# 23_LMS2_RX1_BB_ADC.net
KiCad netlist of a schematic drawn in Altium Designer
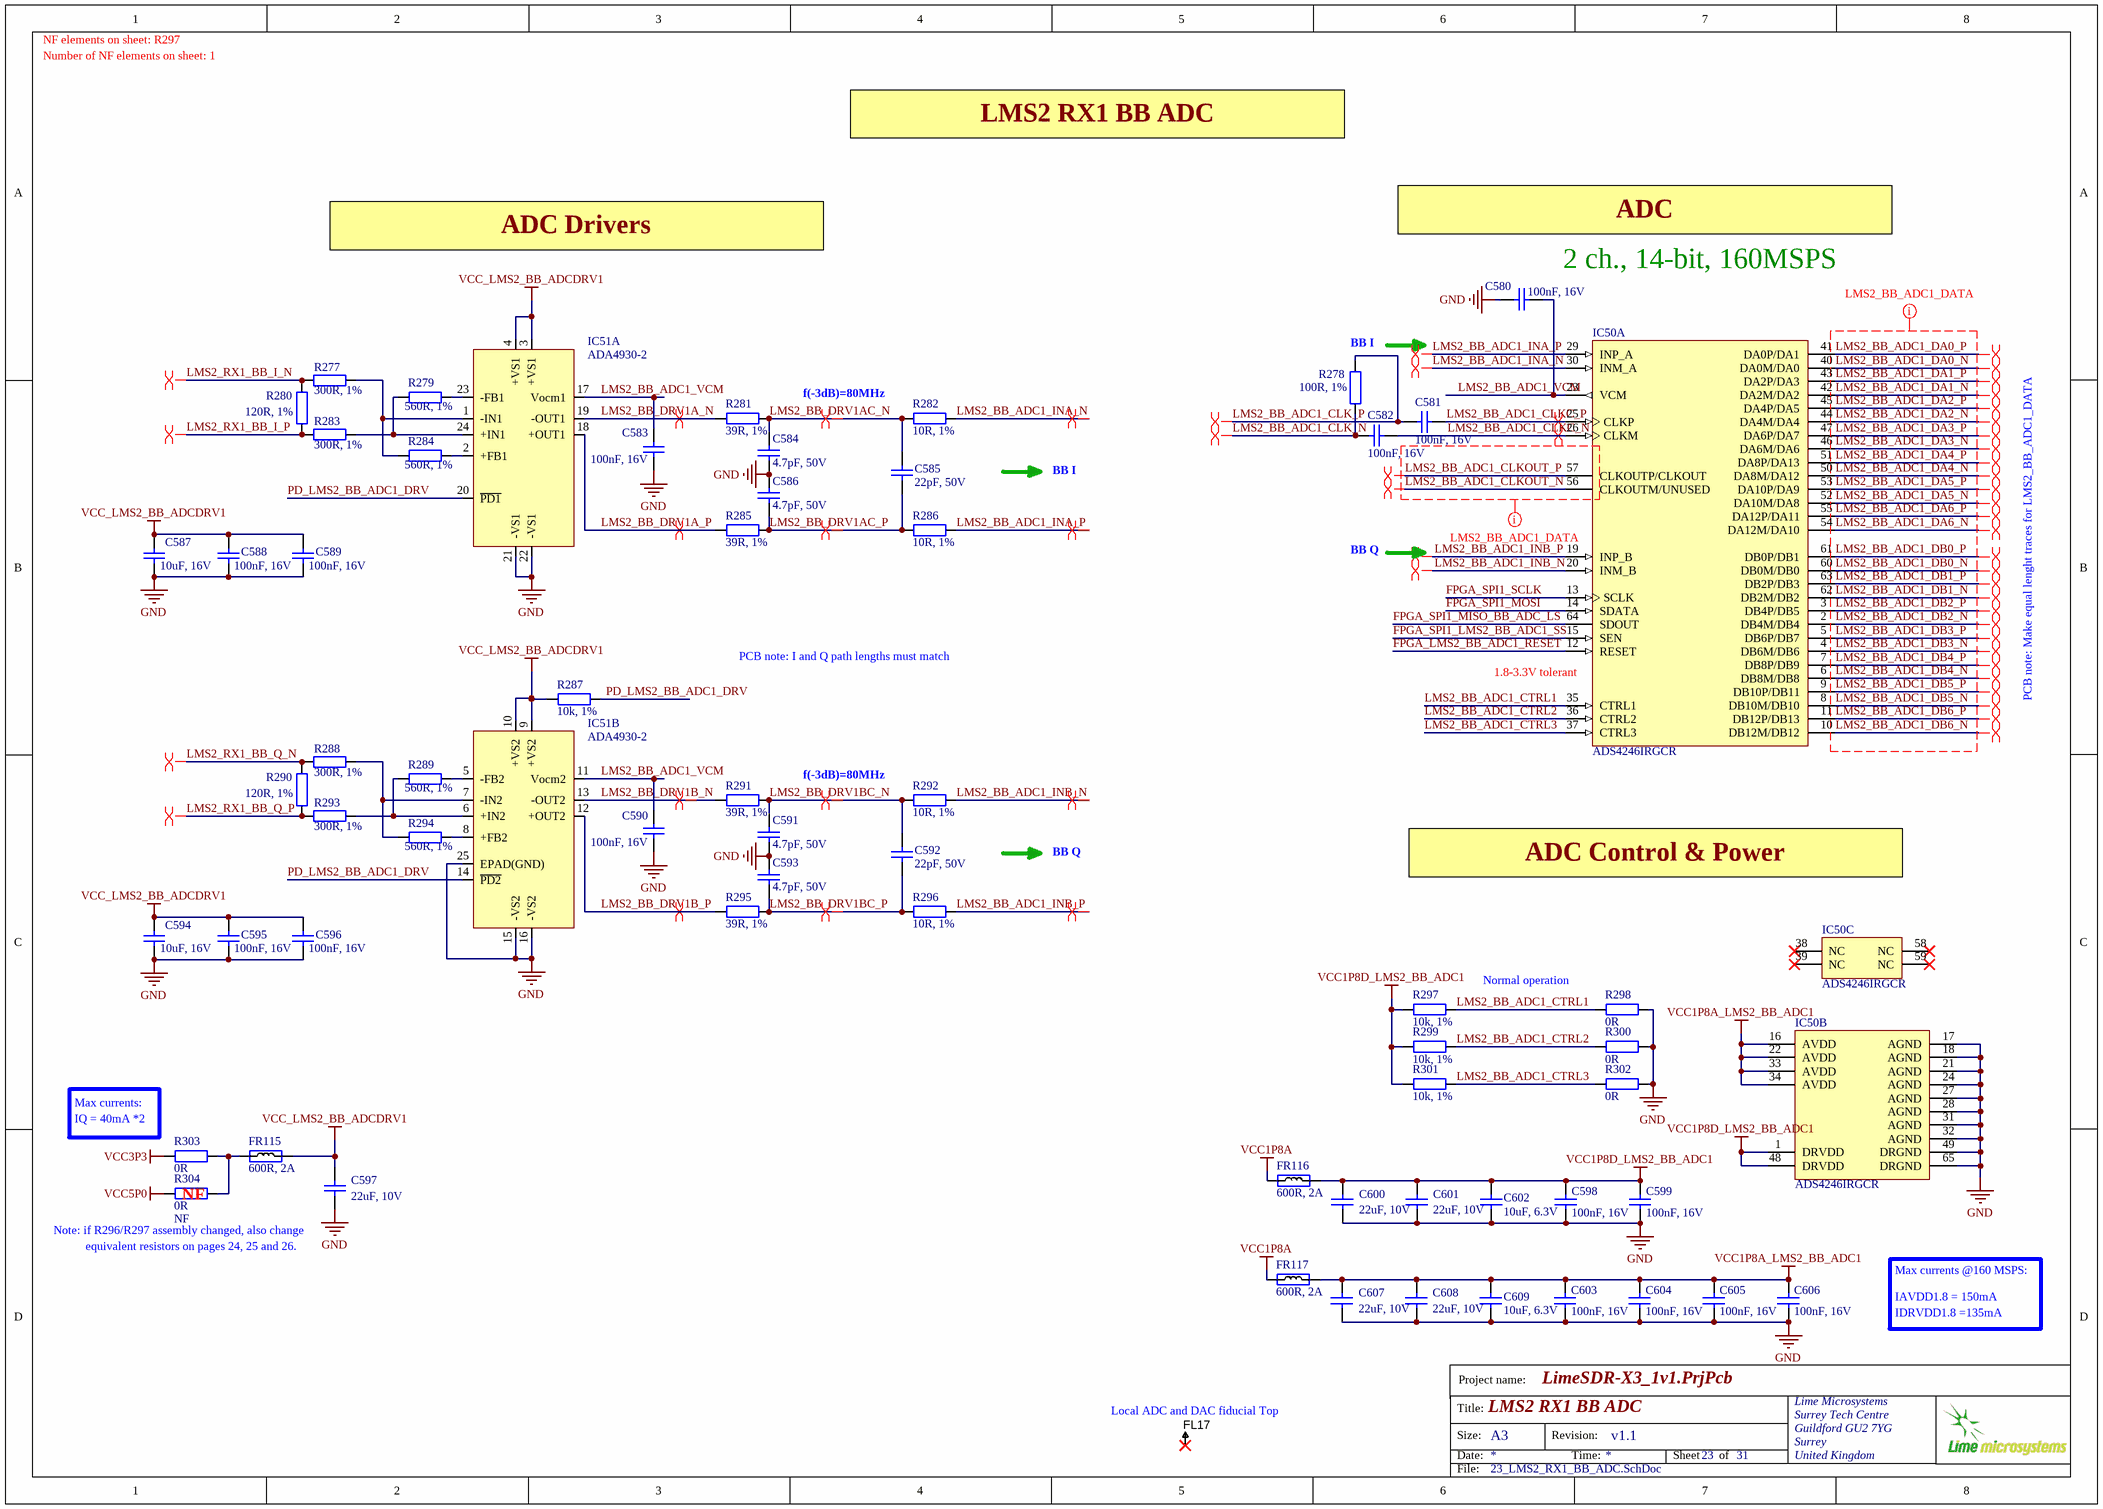
[diagram p0: 23_LMS2_RX1_BB_ADC.SchDoc]

(export (version "E")
  (design (tool "Eeschema 10.0.6"))
  (components
    (comp (ref "C580")
      (value "100nF, 16V")
      (footprint "CAP0402")
      (fields (field (name "TOLERANCE") "10 %") (field (name "MANUFACTURER") "Murata Electronics"))
      (libsource (lib "") (part "Cap_0603_2"))
    )
    (comp (ref "C581")
      (value "100nF, 16V")
      (footprint "CAP0402")
      (fields (field (name "TOLERANCE") "10 %") (field (name "MANUFACTURER") "Murata Electronics"))
      (libsource (lib "") (part "Cap_0603_2"))
    )
    (comp (ref "C582")
      (value "100nF, 16V")
      (footprint "CAP0402")
      (fields (field (name "TOLERANCE") "10 %") (field (name "MANUFACTURER") "Murata Electronics"))
      (libsource (lib "LimeFPGAboard_schLib") (part "Cap_0603"))
    )
    (comp (ref "C583")
      (value "100nF, 16V")
      (footprint "CAP0402")
      (fields (field (name "TOLERANCE") "10 %") (field (name "MANUFACTURER") "Murata Electronics"))
      (libsource (lib "LimeFPGAboard_schLib") (part "Cap_0603"))
    )
    (comp (ref "C584")
      (value "4.7pF, 50V")
      (footprint "CAP0402")
      (fields (field (name "MANUFACTURER") "MURATA"))
      (libsource (lib "LimeMicroAltiumLib_schLib") (part "Cap_0402"))
    )
    (comp (ref "C585")
      (value "22pF, 50V")
      (footprint "CAP0402")
      (fields (field (name "TOLERANCE") "±5%") (field (name "MANUFACTURER") "Yageo"))
      (libsource (lib "") (part "Cap_0402_1"))
    )
    (comp (ref "C586")
      (value "4.7pF, 50V")
      (footprint "CAP0402")
      (fields (field (name "MANUFACTURER") "MURATA"))
      (libsource (lib "LimeMicroAltiumLib_schLib") (part "Cap_0402"))
    )
    (comp (ref "C587")
      (value "10uF, 16V")
      (footprint "CAP0603")
      (fields (field (name "MANUFACTURER") "Yageo") (field (name "TOLERANCE") "±20%"))
      (libsource (lib "LimeMicroAltiumLib_schLib") (part "Cap_0603"))
    )
    (comp (ref "C588")
      (value "100nF, 16V")
      (footprint "CAP0402")
      (fields (field (name "TOLERANCE") "10 %") (field (name "MANUFACTURER") "Murata Electronics"))
      (libsource (lib "LimeFPGAboard_schLib") (part "Cap_0603"))
    )
    (comp (ref "C589")
      (value "100nF, 16V")
      (footprint "CAP0402")
      (fields (field (name "TOLERANCE") "10 %") (field (name "MANUFACTURER") "Murata Electronics"))
      (libsource (lib "LimeFPGAboard_schLib") (part "Cap_0603"))
    )
    (comp (ref "C590")
      (value "100nF, 16V")
      (footprint "CAP0402")
      (fields (field (name "TOLERANCE") "10 %") (field (name "MANUFACTURER") "Murata Electronics"))
      (libsource (lib "") (part "Cap_0603_6"))
    )
    (comp (ref "C591")
      (value "4.7pF, 50V")
      (footprint "CAP0402")
      (fields (field (name "MANUFACTURER") "MURATA"))
      (libsource (lib "LimeMicroAltiumLib_schLib") (part "Cap_0402"))
    )
    (comp (ref "C592")
      (value "22pF, 50V")
      (footprint "CAP0402")
      (fields (field (name "TOLERANCE") "±5%") (field (name "MANUFACTURER") "Yageo"))
      (libsource (lib "") (part "Cap_0402_1"))
    )
    (comp (ref "C593")
      (value "4.7pF, 50V")
      (footprint "CAP0402")
      (fields (field (name "MANUFACTURER") "MURATA"))
      (libsource (lib "LimeMicroAltiumLib_schLib") (part "Cap_0402"))
    )
    (comp (ref "C594")
      (value "10uF, 16V")
      (footprint "CAP0603")
      (fields (field (name "MANUFACTURER") "Yageo") (field (name "TOLERANCE") "±20%"))
      (libsource (lib "LimeMicroAltiumLib_schLib") (part "Cap_0603"))
    )
    (comp (ref "C595")
      (value "100nF, 16V")
      (footprint "CAP0402")
      (fields (field (name "TOLERANCE") "10 %") (field (name "MANUFACTURER") "Murata Electronics"))
      (libsource (lib "LimeFPGAboard_schLib") (part "Cap_0603"))
    )
    (comp (ref "C596")
      (value "100nF, 16V")
      (footprint "CAP0402")
      (fields (field (name "TOLERANCE") "10 %") (field (name "MANUFACTURER") "Murata Electronics"))
      (libsource (lib "LimeFPGAboard_schLib") (part "Cap_0603"))
    )
    (comp (ref "C597")
      (value "22uF, 10V")
      (footprint "CAP0603")
      (fields (field (name "TOLERANCE") "20 %") (field (name "MANUFACTURER") "TDK Corporation"))
      (libsource (lib "") (part "Cap_0603_7"))
    )
    (comp (ref "C598")
      (value "100nF, 16V")
      (footprint "CAP0402")
      (fields (field (name "TOLERANCE") "10 %") (field (name "MANUFACTURER") "Murata Electronics"))
      (libsource (lib "") (part "Cap_0603_5"))
    )
    (comp (ref "C599")
      (value "100nF, 16V")
      (footprint "CAP0402")
      (fields (field (name "TOLERANCE") "10 %") (field (name "MANUFACTURER") "Murata Electronics"))
      (libsource (lib "") (part "Cap_0603_5"))
    )
    (comp (ref "C600")
      (value "22uF, 10V")
      (footprint "CAP0603")
      (fields (field (name "TOLERANCE") "20 %") (field (name "MANUFACTURER") "TDK Corporation"))
      (libsource (lib "") (part "Cap_0603_5"))
    )
    (comp (ref "C601")
      (value "22uF, 10V")
      (footprint "CAP0603")
      (fields (field (name "TOLERANCE") "20 %") (field (name "MANUFACTURER") "TDK Corporation"))
      (libsource (lib "") (part "Cap_0603_5"))
    )
    (comp (ref "C602")
      (value "10uF, 6.3V")
      (footprint "CAP0603")
      (fields (field (name "TOLERANCE") "±20%") (field (name "MANUFACTURER") "Yageo"))
      (libsource (lib "") (part "Cap_0603_1"))
    )
    (comp (ref "C603")
      (value "100nF, 16V")
      (footprint "CAP0402")
      (fields (field (name "TOLERANCE") "10 %") (field (name "MANUFACTURER") "Murata Electronics"))
      (libsource (lib "") (part "Cap_0603_3"))
    )
    (comp (ref "C604")
      (value "100nF, 16V")
      (footprint "CAP0402")
      (fields (field (name "TOLERANCE") "10 %") (field (name "MANUFACTURER") "Murata Electronics"))
      (libsource (lib "") (part "Cap_0603_3"))
    )
    (comp (ref "C605")
      (value "100nF, 16V")
      (footprint "CAP0402")
      (fields (field (name "TOLERANCE") "10 %") (field (name "MANUFACTURER") "Murata Electronics"))
      (libsource (lib "") (part "Cap_0603_3"))
    )
    (comp (ref "C606")
      (value "100nF, 16V")
      (footprint "CAP0402")
      (fields (field (name "TOLERANCE") "10 %") (field (name "MANUFACTURER") "Murata Electronics"))
      (libsource (lib "") (part "Cap_0603_3"))
    )
    (comp (ref "C607")
      (value "22uF, 10V")
      (footprint "CAP0603")
      (fields (field (name "TOLERANCE") "20 %") (field (name "MANUFACTURER") "TDK Corporation"))
      (libsource (lib "") (part "Cap_0603_3"))
    )
    (comp (ref "C608")
      (value "22uF, 10V")
      (footprint "CAP0603")
      (fields (field (name "TOLERANCE") "20 %") (field (name "MANUFACTURER") "TDK Corporation"))
      (libsource (lib "") (part "Cap_0603_3"))
    )
    (comp (ref "C609")
      (value "10uF, 6.3V")
      (footprint "CAP0603")
      (fields (field (name "TOLERANCE") "±20%") (field (name "MANUFACTURER") "Yageo"))
      (libsource (lib "") (part "Cap_0603_4"))
    )
    (comp (ref "FL17")
      (value "Fiducial")
      (footprint "Fiducial_local")
      (libsource (lib "LimeMicroAltiumLib_schLib") (part "Fiducial"))
    )
    (comp (ref "FR115")
      (value "600R, 2A")
      (footprint "RES0805")
      (fields (field (name "MANUFACTURER") "TDK Corporation"))
      (libsource (lib "LimeMicroAltiumLib_schLib") (part "Ferrite"))
    )
    (comp (ref "FR116")
      (value "600R, 2A")
      (footprint "RES0805")
      (fields (field (name "MANUFACTURER") "TDK Corporation"))
      (libsource (lib "LimeFPGAboard_schLib") (part "Ferrite"))
    )
    (comp (ref "FR117")
      (value "600R, 2A")
      (footprint "RES0805")
      (fields (field (name "MANUFACTURER") "TDK Corporation"))
      (libsource (lib "LimeFPGAboard_schLib") (part "Ferrite"))
    )
    (comp (ref "IC50")
      (value "ADS4246IRGCR")
      (footprint "TI-RGC64-7400X7400TP_V")
      (description "14-Bit 160 MSPS Dual Low Power ADC, -40 to 85 degC, 64-pin QFN (RGC64), Green (RoHS & no Sb/Br)")
      (fields (field (name "MANUFACTURER") "Texas Instruments"))
      (libsource (lib "") (part "ADS4246IRGCR_1"))
    )
    (comp (ref "IC51")
      (value "ADA4930-2")
      (footprint "ADA4930-2_LFCSP-24")
      (fields (field (name "MANUFACTURER") "Analog Devices Inc."))
      (libsource (lib "LimeMicroAltiumLib_schLib") (part "ADA4930-2"))
    )
    (comp (ref "R277")
      (value "300R, 1%")
      (footprint "RES0402")
      (fields (field (name "TOLERANCE") "±1%") (field (name "MANUFACTURER") "Vishay Dale"))
      (libsource (lib "LimeFPGAboard_schLib") (part "Res_0402"))
    )
    (comp (ref "R278")
      (value "100R, 1%")
      (footprint "RES0402")
      (fields (field (name "TOLERANCE") "±1%") (field (name "MANUFACTURER") "Stackpole Electronics Inc."))
      (libsource (lib "LimeFPGAboard_schLib") (part "Res_0402"))
    )
    (comp (ref "R279")
      (value "560R, 1%")
      (footprint "RES0402")
      (fields (field (name "TOLERANCE") "±1%") (field (name "MANUFACTURER") "Vishay Dale"))
      (libsource (lib "LimeFPGAboard_schLib") (part "Res_0402"))
    )
    (comp (ref "R280")
      (value "120R, 1%")
      (footprint "RES0402")
      (fields (field (name "MANUFACTURER") "Yageo") (field (name "TOLERANCE") "1%"))
      (libsource (lib "") (part "Res_0402_1"))
    )
    (comp (ref "R281")
      (value "39R, 1%")
      (footprint "RES0402")
      (fields (field (name "MANUFACTURER") "Yageo") (field (name "TOLERANCE") "1%"))
      (libsource (lib "LimeMicroAltiumLib_schLib") (part "Res_0402"))
    )
    (comp (ref "R282")
      (value "10R, 1%")
      (footprint "RES0402")
      (fields (field (name "TOLERANCE") "1%"))
      (libsource (lib "LimeMicroAltiumLib_schLib") (part "Res_0402"))
    )
    (comp (ref "R283")
      (value "300R, 1%")
      (footprint "RES0402")
      (fields (field (name "TOLERANCE") "±1%") (field (name "MANUFACTURER") "Vishay Dale"))
      (libsource (lib "LimeFPGAboard_schLib") (part "Res_0402"))
    )
    (comp (ref "R284")
      (value "560R, 1%")
      (footprint "RES0402")
      (fields (field (name "TOLERANCE") "±1%") (field (name "MANUFACTURER") "Vishay Dale"))
      (libsource (lib "LimeFPGAboard_schLib") (part "Res_0402"))
    )
    (comp (ref "R285")
      (value "39R, 1%")
      (footprint "RES0402")
      (fields (field (name "MANUFACTURER") "Yageo") (field (name "TOLERANCE") "1%"))
      (libsource (lib "LimeMicroAltiumLib_schLib") (part "Res_0402"))
    )
    (comp (ref "R286")
      (value "10R, 1%")
      (footprint "RES0402")
      (fields (field (name "TOLERANCE") "1%"))
      (libsource (lib "LimeMicroAltiumLib_schLib") (part "Res_0402"))
    )
    (comp (ref "R287")
      (value "10k, 1%")
      (footprint "RES0402")
      (fields (field (name "MANUFACTURER") "Yageo") (field (name "TOLERANCE") "±1%"))
      (libsource (lib "LimeMicroAltiumLib_schLib") (part "Res_0402"))
    )
    (comp (ref "R288")
      (value "300R, 1%")
      (footprint "RES0402")
      (fields (field (name "TOLERANCE") "±1%") (field (name "MANUFACTURER") "Vishay Dale"))
      (libsource (lib "LimeFPGAboard_schLib") (part "Res_0402"))
    )
    (comp (ref "R289")
      (value "560R, 1%")
      (footprint "RES0402")
      (fields (field (name "TOLERANCE") "±1%") (field (name "MANUFACTURER") "Vishay Dale"))
      (libsource (lib "LimeFPGAboard_schLib") (part "Res_0402"))
    )
    (comp (ref "R290")
      (value "120R, 1%")
      (footprint "RES0402")
      (fields (field (name "MANUFACTURER") "Yageo") (field (name "TOLERANCE") "1%"))
      (libsource (lib "") (part "Res_0402_1"))
    )
    (comp (ref "R291")
      (value "39R, 1%")
      (footprint "RES0402")
      (fields (field (name "MANUFACTURER") "Yageo") (field (name "TOLERANCE") "1%"))
      (libsource (lib "LimeMicroAltiumLib_schLib") (part "Res_0402"))
    )
    (comp (ref "R292")
      (value "10R, 1%")
      (footprint "RES0402")
      (fields (field (name "TOLERANCE") "1%"))
      (libsource (lib "LimeMicroAltiumLib_schLib") (part "Res_0402"))
    )
    (comp (ref "R293")
      (value "300R, 1%")
      (footprint "RES0402")
      (fields (field (name "TOLERANCE") "±1%") (field (name "MANUFACTURER") "Vishay Dale"))
      (libsource (lib "LimeFPGAboard_schLib") (part "Res_0402"))
    )
    (comp (ref "R294")
      (value "560R, 1%")
      (footprint "RES0402")
      (fields (field (name "TOLERANCE") "±1%") (field (name "MANUFACTURER") "Vishay Dale"))
      (libsource (lib "LimeFPGAboard_schLib") (part "Res_0402"))
    )
    (comp (ref "R295")
      (value "39R, 1%")
      (footprint "RES0402")
      (fields (field (name "MANUFACTURER") "Yageo") (field (name "TOLERANCE") "1%"))
      (libsource (lib "LimeMicroAltiumLib_schLib") (part "Res_0402"))
    )
    (comp (ref "R296")
      (value "10R, 1%")
      (footprint "RES0402")
      (fields (field (name "TOLERANCE") "1%"))
      (libsource (lib "LimeMicroAltiumLib_schLib") (part "Res_0402"))
    )
    (comp (ref "R297")
      (value "10k, 1%")
      (footprint "RES0402")
      (fields (field (name "MANUFACTURER") "Yageo") (field (name "TOLERANCE") "±1%"))
      (libsource (lib "LimeMicroAltiumLib_schLib") (part "Res_0402"))
    )
    (comp (ref "R298")
      (value "0R")
      (footprint "RES0402")
      (fields (field (name "MANUFACTURER") "Yageo"))
      (libsource (lib "LimeFPGAboard_schLib") (part "Res_0402"))
    )
    (comp (ref "R299")
      (value "10k, 1%")
      (footprint "RES0402")
      (fields (field (name "MANUFACTURER") "Yageo") (field (name "TOLERANCE") "±1%"))
      (libsource (lib "LimeMicroAltiumLib_schLib") (part "Res_0402"))
    )
    (comp (ref "R300")
      (value "0R")
      (footprint "RES0402")
      (fields (field (name "MANUFACTURER") "Yageo"))
      (libsource (lib "LimeFPGAboard_schLib") (part "Res_0402"))
    )
    (comp (ref "R301")
      (value "10k, 1%")
      (footprint "RES0402")
      (fields (field (name "MANUFACTURER") "Yageo") (field (name "TOLERANCE") "±1%"))
      (libsource (lib "LimeMicroAltiumLib_schLib") (part "Res_0402"))
    )
    (comp (ref "R302")
      (value "0R")
      (footprint "RES0402")
      (fields (field (name "MANUFACTURER") "Yageo"))
      (libsource (lib "LimeFPGAboard_schLib") (part "Res_0402"))
    )
    (comp (ref "R303")
      (value "0R")
      (footprint "RES0402")
      (fields (field (name "MANUFACTURER") "Yageo") (field (name "TOLERANCE") "Jumper"))
      (libsource (lib "LimeMicroAltiumLib_schLib") (part "Res_0402"))
    )
    (comp (ref "R304")
      (value "0R")
      (footprint "RES0402")
      (fields
        (field (name "ASSEMBLY INFO") "NF")
        (field (name "MANUFACTURER") "Yageo")
        (field (name "TOLERANCE") "Jumper")
      )
      (libsource (lib "LimeMicroAltiumLib_schLib") (part "Res_0402"))
    )
  )
  (nets
    (net (code "1") (name "/FPGA_LMS2_BB_ADC1_RESET") (class "Default")
      (node (ref "IC50") (pin "12") (pinfunction "RESET_12") (pintype "input"))
    )
    (net (code "2") (name "/FPGA_SPI1_LMS2_BB_ADC1_SS") (class "Default")
      (node (ref "IC50") (pin "15") (pinfunction "SEN_15") (pintype "input"))
    )
    (net (code "3") (name "/FPGA_SPI1_MISO_BB_ADC_LS") (class "Default")
      (node (ref "IC50") (pin "64") (pinfunction "SDOUT_64") (pintype "tri_state"))
    )
    (net (code "4") (name "/FPGA_SPI1_MOSI") (class "Default")
      (node (ref "IC50") (pin "14") (pinfunction "SDATA_14") (pintype "input"))
    )
    (net (code "5") (name "/FPGA_SPI1_SCLK") (class "Default")
      (node (ref "IC50") (pin "13") (pinfunction "SCLK_13") (pintype "input"))
    )
    (net (code "6") (name "/LMS2_BB_ADC1_CLKC_N") (class "Default")
      (node (ref "C582") (pin "1") (pinfunction "1_1") (pintype "passive"))
      (node (ref "IC50") (pin "26") (pinfunction "CLKM_26") (pintype "input"))
    )
    (net (code "7") (name "/LMS2_BB_ADC1_CLKC_P") (class "Default")
      (node (ref "C581") (pin "1") (pinfunction "1_1") (pintype "passive"))
      (node (ref "IC50") (pin "25") (pinfunction "CLKP_25") (pintype "input"))
    )
    (net (code "8") (name "/LMS2_BB_ADC1_CLKOUT_N") (class "Default")
      (node (ref "IC50") (pin "56") (pinfunction "CLKOUTM/UNUSED_56") (pintype "tri_state"))
    )
    (net (code "9") (name "/LMS2_BB_ADC1_CLKOUT_P") (class "Default")
      (node (ref "IC50") (pin "57") (pinfunction "CLKOUTP/CLKOUT_57") (pintype "tri_state"))
    )
    (net (code "10") (name "/LMS2_BB_ADC1_CLK_N") (class "Default")
      (node (ref "C582") (pin "2") (pinfunction "2_2") (pintype "passive"))
      (node (ref "R278") (pin "1") (pinfunction "1_1") (pintype "passive"))
    )
    (net (code "11") (name "/LMS2_BB_ADC1_CLK_P") (class "Default")
      (node (ref "C581") (pin "2") (pinfunction "2_2") (pintype "passive"))
      (node (ref "R278") (pin "2") (pinfunction "2_2") (pintype "passive"))
    )
    (net (code "12") (name "/LMS2_BB_ADC1_CTRL1") (class "Default")
      (node (ref "IC50") (pin "35") (pinfunction "CTRL1_35") (pintype "input"))
      (node (ref "R297") (pin "1") (pinfunction "1_1") (pintype "passive"))
      (node (ref "R298") (pin "2") (pinfunction "2_2") (pintype "passive"))
    )
    (net (code "13") (name "/LMS2_BB_ADC1_CTRL2") (class "Default")
      (node (ref "IC50") (pin "36") (pinfunction "CTRL2_36") (pintype "input"))
      (node (ref "R299") (pin "1") (pinfunction "1_1") (pintype "passive"))
      (node (ref "R300") (pin "2") (pinfunction "2_2") (pintype "passive"))
    )
    (net (code "14") (name "/LMS2_BB_ADC1_CTRL3") (class "Default")
      (node (ref "IC50") (pin "37") (pinfunction "CTRL3_37") (pintype "input"))
      (node (ref "R301") (pin "1") (pinfunction "1_1") (pintype "passive"))
      (node (ref "R302") (pin "2") (pinfunction "2_2") (pintype "passive"))
    )
    (net (code "15") (name "/LMS2_BB_ADC1_DA0_N") (class "Default")
      (node (ref "IC50") (pin "40") (pinfunction "DA0M/DA0_40") (pintype "tri_state"))
    )
    (net (code "16") (name "/LMS2_BB_ADC1_DA0_P") (class "Default")
      (node (ref "IC50") (pin "41") (pinfunction "DA0P/DA1_41") (pintype "tri_state"))
    )
    (net (code "17") (name "/LMS2_BB_ADC1_DA1_N") (class "Default")
      (node (ref "IC50") (pin "42") (pinfunction "DA2M/DA2_42") (pintype "tri_state"))
    )
    (net (code "18") (name "/LMS2_BB_ADC1_DA1_P") (class "Default")
      (node (ref "IC50") (pin "43") (pinfunction "DA2P/DA3_43") (pintype "tri_state"))
    )
    (net (code "19") (name "/LMS2_BB_ADC1_DA2_N") (class "Default")
      (node (ref "IC50") (pin "44") (pinfunction "DA4M/DA4_44") (pintype "tri_state"))
    )
    (net (code "20") (name "/LMS2_BB_ADC1_DA2_P") (class "Default")
      (node (ref "IC50") (pin "45") (pinfunction "DA4P/DA5_45") (pintype "tri_state"))
    )
    (net (code "21") (name "/LMS2_BB_ADC1_DA3_N") (class "Default")
      (node (ref "IC50") (pin "46") (pinfunction "DA6M/DA6_46") (pintype "tri_state"))
    )
    (net (code "22") (name "/LMS2_BB_ADC1_DA3_P") (class "Default")
      (node (ref "IC50") (pin "47") (pinfunction "DA6P/DA7_47") (pintype "tri_state"))
    )
    (net (code "23") (name "/LMS2_BB_ADC1_DA4_N") (class "Default")
      (node (ref "IC50") (pin "50") (pinfunction "DA8M/DA12_50") (pintype "tri_state"))
    )
    (net (code "24") (name "/LMS2_BB_ADC1_DA4_P") (class "Default")
      (node (ref "IC50") (pin "51") (pinfunction "DA8P/DA13_51") (pintype "tri_state"))
    )
    (net (code "25") (name "/LMS2_BB_ADC1_DA5_N") (class "Default")
      (node (ref "IC50") (pin "52") (pinfunction "DA10M/DA8_52") (pintype "tri_state"))
    )
    (net (code "26") (name "/LMS2_BB_ADC1_DA5_P") (class "Default")
      (node (ref "IC50") (pin "53") (pinfunction "DA10P/DA9_53") (pintype "tri_state"))
    )
    (net (code "27") (name "/LMS2_BB_ADC1_DA6_N") (class "Default")
      (node (ref "IC50") (pin "54") (pinfunction "DA12M/DA10_54") (pintype "tri_state"))
    )
    (net (code "28") (name "/LMS2_BB_ADC1_DA6_P") (class "Default")
      (node (ref "IC50") (pin "55") (pinfunction "DA12P/DA11_55") (pintype "tri_state"))
    )
    (net (code "29") (name "/LMS2_BB_ADC1_DB0_N") (class "Default")
      (node (ref "IC50") (pin "60") (pinfunction "DB0M/DB0_60") (pintype "tri_state"))
    )
    (net (code "30") (name "/LMS2_BB_ADC1_DB0_P") (class "Default")
      (node (ref "IC50") (pin "61") (pinfunction "DB0P/DB1_61") (pintype "tri_state"))
    )
    (net (code "31") (name "/LMS2_BB_ADC1_DB1_N") (class "Default")
      (node (ref "IC50") (pin "62") (pinfunction "DB2M/DB2_62") (pintype "tri_state"))
    )
    (net (code "32") (name "/LMS2_BB_ADC1_DB1_P") (class "Default")
      (node (ref "IC50") (pin "63") (pinfunction "DB2P/DB3_63") (pintype "tri_state"))
    )
    (net (code "33") (name "/LMS2_BB_ADC1_DB2_N") (class "Default")
      (node (ref "IC50") (pin "2") (pinfunction "DB4M/DB4_2") (pintype "tri_state"))
    )
    (net (code "34") (name "/LMS2_BB_ADC1_DB2_P") (class "Default")
      (node (ref "IC50") (pin "3") (pinfunction "DB4P/DB5_3") (pintype "tri_state"))
    )
    (net (code "35") (name "/LMS2_BB_ADC1_DB3_N") (class "Default")
      (node (ref "IC50") (pin "4") (pinfunction "DB6M/DB6_4") (pintype "tri_state"))
    )
    (net (code "36") (name "/LMS2_BB_ADC1_DB3_P") (class "Default")
      (node (ref "IC50") (pin "5") (pinfunction "DB6P/DB7_5") (pintype "tri_state"))
    )
    (net (code "37") (name "/LMS2_BB_ADC1_DB4_N") (class "Default")
      (node (ref "IC50") (pin "6") (pinfunction "DB8M/DB8_6") (pintype "tri_state"))
    )
    (net (code "38") (name "/LMS2_BB_ADC1_DB4_P") (class "Default")
      (node (ref "IC50") (pin "7") (pinfunction "DB8P/DB9_7") (pintype "tri_state"))
    )
    (net (code "39") (name "/LMS2_BB_ADC1_DB5_N") (class "Default")
      (node (ref "IC50") (pin "8") (pinfunction "DB10M/DB10_8") (pintype "tri_state"))
    )
    (net (code "40") (name "/LMS2_BB_ADC1_DB5_P") (class "Default")
      (node (ref "IC50") (pin "9") (pinfunction "DB10P/DB11_9") (pintype "tri_state"))
    )
    (net (code "41") (name "/LMS2_BB_ADC1_DB6_N") (class "Default")
      (node (ref "IC50") (pin "10") (pinfunction "DB12M/DB12_10") (pintype "tri_state"))
    )
    (net (code "42") (name "/LMS2_BB_ADC1_DB6_P") (class "Default")
      (node (ref "IC50") (pin "11") (pinfunction "DB12P/DB13_11") (pintype "tri_state"))
    )
    (net (code "43") (name "/LMS2_BB_ADC1_INA_N") (class "Default")
      (node (ref "IC50") (pin "30") (pinfunction "INM_A_30") (pintype "input"))
      (node (ref "R282") (pin "1") (pinfunction "1_1") (pintype "passive"))
    )
    (net (code "44") (name "/LMS2_BB_ADC1_INA_P") (class "Default")
      (node (ref "IC50") (pin "29") (pinfunction "INP_A_29") (pintype "input"))
      (node (ref "R286") (pin "1") (pinfunction "1_1") (pintype "passive"))
    )
    (net (code "45") (name "/LMS2_BB_ADC1_INB_N") (class "Default")
      (node (ref "IC50") (pin "20") (pinfunction "INM_B_20") (pintype "input"))
      (node (ref "R292") (pin "1") (pinfunction "1_1") (pintype "passive"))
    )
    (net (code "46") (name "/LMS2_BB_ADC1_INB_P") (class "Default")
      (node (ref "IC50") (pin "19") (pinfunction "INP_B_19") (pintype "input"))
      (node (ref "R296") (pin "1") (pinfunction "1_1") (pintype "passive"))
    )
    (net (code "47") (name "/LMS2_BB_ADC1_VCM") (class "Default")
      (node (ref "C580") (pin "2") (pinfunction "2_2") (pintype "passive"))
      (node (ref "C583") (pin "1") (pinfunction "1_1") (pintype "passive"))
      (node (ref "C590") (pin "1") (pinfunction "1_1") (pintype "passive"))
      (node (ref "IC50") (pin "23") (pinfunction "VCM_23") (pintype "output"))
      (node (ref "IC51") (pin "11") (pinfunction "Vocm2_11") (pintype "input"))
      (node (ref "IC51") (pin "17") (pinfunction "Vocm1_17") (pintype "input"))
    )
    (net (code "48") (name "/LMS2_BB_DRV1AC_N") (class "Default")
      (node (ref "C584") (pin "1") (pinfunction "1_1") (pintype "passive"))
      (node (ref "C585") (pin "1") (pinfunction "1_1") (pintype "passive"))
      (node (ref "R281") (pin "1") (pinfunction "1_1") (pintype "passive"))
      (node (ref "R282") (pin "2") (pinfunction "2_2") (pintype "passive"))
    )
    (net (code "49") (name "/LMS2_BB_DRV1AC_P") (class "Default")
      (node (ref "C585") (pin "2") (pinfunction "2_2") (pintype "passive"))
      (node (ref "C586") (pin "2") (pinfunction "2_2") (pintype "passive"))
      (node (ref "R285") (pin "1") (pinfunction "1_1") (pintype "passive"))
      (node (ref "R286") (pin "2") (pinfunction "2_2") (pintype "passive"))
    )
    (net (code "50") (name "/LMS2_BB_DRV1A_N") (class "Default")
      (node (ref "IC51") (pin "19") (pinfunction "-OUT1_19") (pintype "output"))
      (node (ref "R281") (pin "2") (pinfunction "2_2") (pintype "passive"))
    )
    (net (code "51") (name "/LMS2_BB_DRV1A_P") (class "Default")
      (node (ref "IC51") (pin "18") (pinfunction "+OUT1_18") (pintype "output"))
      (node (ref "R285") (pin "2") (pinfunction "2_2") (pintype "passive"))
    )
    (net (code "52") (name "/LMS2_BB_DRV1BC_N") (class "Default")
      (node (ref "C591") (pin "1") (pinfunction "1_1") (pintype "passive"))
      (node (ref "C592") (pin "1") (pinfunction "1_1") (pintype "passive"))
      (node (ref "R291") (pin "1") (pinfunction "1_1") (pintype "passive"))
      (node (ref "R292") (pin "2") (pinfunction "2_2") (pintype "passive"))
    )
    (net (code "53") (name "/LMS2_BB_DRV1BC_P") (class "Default")
      (node (ref "C592") (pin "2") (pinfunction "2_2") (pintype "passive"))
      (node (ref "C593") (pin "2") (pinfunction "2_2") (pintype "passive"))
      (node (ref "R295") (pin "1") (pinfunction "1_1") (pintype "passive"))
      (node (ref "R296") (pin "2") (pinfunction "2_2") (pintype "passive"))
    )
    (net (code "54") (name "/LMS2_BB_DRV1B_N") (class "Default")
      (node (ref "IC51") (pin "13") (pinfunction "-OUT2_13") (pintype "output"))
      (node (ref "R291") (pin "2") (pinfunction "2_2") (pintype "passive"))
    )
    (net (code "55") (name "/LMS2_BB_DRV1B_P") (class "Default")
      (node (ref "IC51") (pin "12") (pinfunction "+OUT2_12") (pintype "output"))
      (node (ref "R295") (pin "2") (pinfunction "2_2") (pintype "passive"))
    )
    (net (code "56") (name "/LMS2_RX1_BB_I_N") (class "Default")
      (node (ref "R277") (pin "2") (pinfunction "2_2") (pintype "passive"))
      (node (ref "R280") (pin "2") (pinfunction "2_2") (pintype "passive"))
    )
    (net (code "57") (name "/LMS2_RX1_BB_I_P") (class "Default")
      (node (ref "R280") (pin "1") (pinfunction "1_1") (pintype "passive"))
      (node (ref "R283") (pin "2") (pinfunction "2_2") (pintype "passive"))
    )
    (net (code "58") (name "/LMS2_RX1_BB_Q_N") (class "Default")
      (node (ref "R288") (pin "2") (pinfunction "2_2") (pintype "passive"))
      (node (ref "R290") (pin "2") (pinfunction "2_2") (pintype "passive"))
    )
    (net (code "59") (name "/LMS2_RX1_BB_Q_P") (class "Default")
      (node (ref "R290") (pin "1") (pinfunction "1_1") (pintype "passive"))
      (node (ref "R293") (pin "2") (pinfunction "2_2") (pintype "passive"))
    )
    (net (code "60") (name "/PD_LMS2_BB_ADC1_DRV") (class "Default")
      (node (ref "IC51") (pin "14") (pinfunction "~{PD2}_14") (pintype "input"))
      (node (ref "IC51") (pin "20") (pinfunction "~{PD1}_20") (pintype "input"))
      (node (ref "R287") (pin "1") (pinfunction "1_1") (pintype "passive"))
    )
    (net (code "61") (name "GND") (class "Default")
      (node (ref "C580") (pin "1") (pinfunction "1_1") (pintype "passive"))
      (node (ref "C583") (pin "2") (pinfunction "2_2") (pintype "passive"))
      (node (ref "C584") (pin "2") (pinfunction "2_2") (pintype "passive"))
      (node (ref "C586") (pin "1") (pinfunction "1_1") (pintype "passive"))
      (node (ref "C587") (pin "1") (pinfunction "1_1") (pintype "passive"))
      (node (ref "C588") (pin "2") (pinfunction "2_2") (pintype "passive"))
      (node (ref "C589") (pin "2") (pinfunction "2_2") (pintype "passive"))
      (node (ref "C590") (pin "2") (pinfunction "2_2") (pintype "passive"))
      (node (ref "C591") (pin "2") (pinfunction "2_2") (pintype "passive"))
      (node (ref "C593") (pin "1") (pinfunction "1_1") (pintype "passive"))
      (node (ref "C594") (pin "1") (pinfunction "1_1") (pintype "passive"))
      (node (ref "C595") (pin "2") (pinfunction "2_2") (pintype "passive"))
      (node (ref "C596") (pin "2") (pinfunction "2_2") (pintype "passive"))
      (node (ref "C597") (pin "1") (pinfunction "1_1") (pintype "passive"))
      (node (ref "C598") (pin "1") (pinfunction "1_1") (pintype "passive"))
      (node (ref "C599") (pin "1") (pinfunction "1_1") (pintype "passive"))
      (node (ref "C600") (pin "1") (pinfunction "1_1") (pintype "passive"))
      (node (ref "C601") (pin "1") (pinfunction "1_1") (pintype "passive"))
      (node (ref "C602") (pin "2") (pinfunction "2_2") (pintype "passive"))
      (node (ref "C603") (pin "1") (pinfunction "1_1") (pintype "passive"))
      (node (ref "C604") (pin "1") (pinfunction "1_1") (pintype "passive"))
      (node (ref "C605") (pin "1") (pinfunction "1_1") (pintype "passive"))
      (node (ref "C606") (pin "1") (pinfunction "1_1") (pintype "passive"))
      (node (ref "C607") (pin "1") (pinfunction "1_1") (pintype "passive"))
      (node (ref "C608") (pin "1") (pinfunction "1_1") (pintype "passive"))
      (node (ref "C609") (pin "2") (pinfunction "2_2") (pintype "passive"))
      (node (ref "IC50") (pin "17") (pinfunction "AGND_17") (pintype "power_in"))
      (node (ref "IC50") (pin "18") (pinfunction "AGND_18") (pintype "power_in"))
      (node (ref "IC50") (pin "21") (pinfunction "AGND_21") (pintype "power_in"))
      (node (ref "IC50") (pin "24") (pinfunction "AGND_24") (pintype "power_in"))
      (node (ref "IC50") (pin "27") (pinfunction "AGND_27") (pintype "power_in"))
      (node (ref "IC50") (pin "28") (pinfunction "AGND_28") (pintype "power_in"))
      (node (ref "IC50") (pin "31") (pinfunction "AGND_31") (pintype "power_in"))
      (node (ref "IC50") (pin "32") (pinfunction "AGND_32") (pintype "power_in"))
      (node (ref "IC50") (pin "49") (pinfunction "DRGND_49") (pintype "power_in"))
      (node (ref "IC50") (pin "65") (pinfunction "DRGND_65") (pintype "power_in"))
      (node (ref "IC51") (pin "15") (pinfunction "-VS2_15") (pintype "power_in"))
      (node (ref "IC51") (pin "16") (pinfunction "-VS2_16") (pintype "power_in"))
      (node (ref "IC51") (pin "21") (pinfunction "-VS1_21") (pintype "power_in"))
      (node (ref "IC51") (pin "22") (pinfunction "-VS1_22") (pintype "power_in"))
      (node (ref "IC51") (pin "25") (pinfunction "EPAD(GND)_25") (pintype "passive"))
      (node (ref "R298") (pin "1") (pinfunction "1_1") (pintype "passive"))
      (node (ref "R300") (pin "1") (pinfunction "1_1") (pintype "passive"))
      (node (ref "R302") (pin "1") (pinfunction "1_1") (pintype "passive"))
    )
    (net (code "62") (name "Net-(FR115-Pad1)") (class "Default")
      (node (ref "FR115") (pin "1") (pinfunction "1_1") (pintype "passive"))
      (node (ref "R303") (pin "1") (pinfunction "1_1") (pintype "passive"))
      (node (ref "R304") (pin "1") (pinfunction "1_1") (pintype "passive"))
    )
    (net (code "63") (name "Net-(IC51A-+FB1)") (class "Default")
      (node (ref "IC51") (pin "2") (pinfunction "+FB1_2") (pintype "output"))
      (node (ref "R284") (pin "1") (pinfunction "1_1") (pintype "passive"))
    )
    (net (code "64") (name "Net-(IC51A-+IN1)") (class "Default")
      (node (ref "IC51") (pin "24") (pinfunction "+IN1_24") (pintype "input"))
      (node (ref "R279") (pin "2") (pinfunction "2_2") (pintype "passive"))
      (node (ref "R283") (pin "1") (pinfunction "1_1") (pintype "passive"))
    )
    (net (code "65") (name "Net-(IC51A--FB1)") (class "Default")
      (node (ref "IC51") (pin "23") (pinfunction "-FB1_23") (pintype "output"))
      (node (ref "R279") (pin "1") (pinfunction "1_1") (pintype "passive"))
    )
    (net (code "66") (name "Net-(IC51A--IN1)") (class "Default")
      (node (ref "IC51") (pin "1") (pinfunction "-IN1_1") (pintype "input"))
      (node (ref "R277") (pin "1") (pinfunction "1_1") (pintype "passive"))
      (node (ref "R284") (pin "2") (pinfunction "2_2") (pintype "passive"))
    )
    (net (code "67") (name "Net-(IC51B-+FB2)") (class "Default")
      (node (ref "IC51") (pin "8") (pinfunction "+FB2_8") (pintype "output"))
      (node (ref "R294") (pin "1") (pinfunction "1_1") (pintype "passive"))
    )
    (net (code "68") (name "Net-(IC51B-+IN2)") (class "Default")
      (node (ref "IC51") (pin "6") (pinfunction "+IN2_6") (pintype "input"))
      (node (ref "R289") (pin "2") (pinfunction "2_2") (pintype "passive"))
      (node (ref "R293") (pin "1") (pinfunction "1_1") (pintype "passive"))
    )
    (net (code "69") (name "Net-(IC51B--FB2)") (class "Default")
      (node (ref "IC51") (pin "5") (pinfunction "-FB2_5") (pintype "output"))
      (node (ref "R289") (pin "1") (pinfunction "1_1") (pintype "passive"))
    )
    (net (code "70") (name "Net-(IC51B--IN2)") (class "Default")
      (node (ref "IC51") (pin "7") (pinfunction "-IN2_7") (pintype "input"))
      (node (ref "R288") (pin "1") (pinfunction "1_1") (pintype "passive"))
      (node (ref "R294") (pin "2") (pinfunction "2_2") (pintype "passive"))
    )
    (net (code "71") (name "VCC1P8A") (class "Default")
      (node (ref "FR116") (pin "1") (pinfunction "1_1") (pintype "passive"))
      (node (ref "FR117") (pin "1") (pinfunction "1_1") (pintype "passive"))
    )
    (net (code "72") (name "VCC1P8A_LMS2_BB_ADC1") (class "Default")
      (node (ref "C603") (pin "2") (pinfunction "2_2") (pintype "passive"))
      (node (ref "C604") (pin "2") (pinfunction "2_2") (pintype "passive"))
      (node (ref "C605") (pin "2") (pinfunction "2_2") (pintype "passive"))
      (node (ref "C606") (pin "2") (pinfunction "2_2") (pintype "passive"))
      (node (ref "C607") (pin "2") (pinfunction "2_2") (pintype "passive"))
      (node (ref "C608") (pin "2") (pinfunction "2_2") (pintype "passive"))
      (node (ref "C609") (pin "1") (pinfunction "1_1") (pintype "passive"))
      (node (ref "FR117") (pin "2") (pinfunction "2_2") (pintype "passive"))
      (node (ref "IC50") (pin "16") (pinfunction "AVDD_16") (pintype "power_in"))
      (node (ref "IC50") (pin "22") (pinfunction "AVDD_22") (pintype "power_in"))
      (node (ref "IC50") (pin "33") (pinfunction "AVDD_33") (pintype "power_in"))
      (node (ref "IC50") (pin "34") (pinfunction "AVDD_34") (pintype "power_in"))
    )
    (net (code "73") (name "VCC1P8D_LMS2_BB_ADC1") (class "Default")
      (node (ref "C598") (pin "2") (pinfunction "2_2") (pintype "passive"))
      (node (ref "C599") (pin "2") (pinfunction "2_2") (pintype "passive"))
      (node (ref "C600") (pin "2") (pinfunction "2_2") (pintype "passive"))
      (node (ref "C601") (pin "2") (pinfunction "2_2") (pintype "passive"))
      (node (ref "C602") (pin "1") (pinfunction "1_1") (pintype "passive"))
      (node (ref "FR116") (pin "2") (pinfunction "2_2") (pintype "passive"))
      (node (ref "IC50") (pin "1") (pinfunction "DRVDD_1") (pintype "power_in"))
      (node (ref "IC50") (pin "48") (pinfunction "DRVDD_48") (pintype "power_in"))
      (node (ref "R297") (pin "2") (pinfunction "2_2") (pintype "passive"))
      (node (ref "R299") (pin "2") (pinfunction "2_2") (pintype "passive"))
      (node (ref "R301") (pin "2") (pinfunction "2_2") (pintype "passive"))
    )
    (net (code "74") (name "VCC3P3") (class "Default")
      (node (ref "R303") (pin "2") (pinfunction "2_2") (pintype "passive"))
    )
    (net (code "75") (name "VCC5P0") (class "Default")
      (node (ref "R304") (pin "2") (pinfunction "2_2") (pintype "passive"))
    )
    (net (code "76") (name "VCC_LMS2_BB_ADCDRV1") (class "Default")
      (node (ref "C587") (pin "2") (pinfunction "2_2") (pintype "passive"))
      (node (ref "C588") (pin "1") (pinfunction "1_1") (pintype "passive"))
      (node (ref "C589") (pin "1") (pinfunction "1_1") (pintype "passive"))
      (node (ref "C594") (pin "2") (pinfunction "2_2") (pintype "passive"))
      (node (ref "C595") (pin "1") (pinfunction "1_1") (pintype "passive"))
      (node (ref "C596") (pin "1") (pinfunction "1_1") (pintype "passive"))
      (node (ref "C597") (pin "2") (pinfunction "2_2") (pintype "passive"))
      (node (ref "FR115") (pin "2") (pinfunction "2_2") (pintype "passive"))
      (node (ref "IC51") (pin "10") (pinfunction "+VS2_10") (pintype "power_in"))
      (node (ref "IC51") (pin "3") (pinfunction "+VS1_3") (pintype "power_in"))
      (node (ref "IC51") (pin "4") (pinfunction "+VS1_4") (pintype "power_in"))
      (node (ref "IC51") (pin "9") (pinfunction "+VS2_9") (pintype "power_in"))
      (node (ref "R287") (pin "2") (pinfunction "2_2") (pintype "passive"))
    )
    (net (code "77") (name "unconnected-(FL17-Pad1)") (class "Default")
      (node (ref "FL17") (pin "1") (pintype "passive+no_connect"))
    )
    (net (code "78") (name "unconnected-(IC50C-NC-Pad38)") (class "Default")
      (node (ref "IC50") (pin "38") (pinfunction "NC_38") (pintype "passive+no_connect"))
    )
    (net (code "79") (name "unconnected-(IC50C-NC-Pad39)") (class "Default")
      (node (ref "IC50") (pin "39") (pinfunction "NC_39") (pintype "passive+no_connect"))
    )
    (net (code "80") (name "unconnected-(IC50C-NC-Pad58)") (class "Default")
      (node (ref "IC50") (pin "58") (pinfunction "NC_58") (pintype "passive+no_connect"))
    )
    (net (code "81") (name "unconnected-(IC50C-NC-Pad59)") (class "Default")
      (node (ref "IC50") (pin "59") (pinfunction "NC_59") (pintype "passive+no_connect"))
    )
  )
)
